# mosfet_board_v1.net
KiCad netlist of a schematic drawn in EAGLE
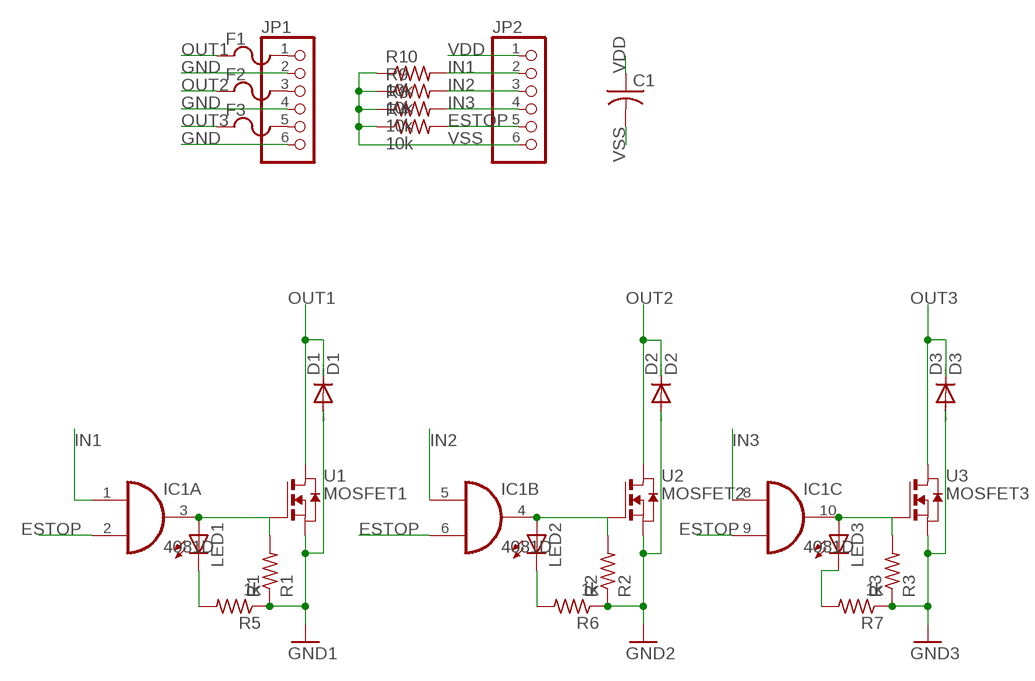
[diagram p0: schematic, sheet 1]

(export (version "E")
  (design (tool "Eeschema 10.0.6"))
  (components
    (comp (ref "C1")
      (value "C-USC0603")
      (footprint "eagle-import:C0603")
      (libsource (lib "eagle-import") (part "C-USC0603"))
    )
    (comp (ref "D1")
      (value "D1")
      (footprint "eagle-import:DO41-10")
      (libsource (lib "eagle-import") (part "1N4004"))
    )
    (comp (ref "D2")
      (value "D2")
      (footprint "eagle-import:DO41-10")
      (libsource (lib "eagle-import") (part "1N4004"))
    )
    (comp (ref "D3")
      (value "D3")
      (footprint "eagle-import:DO41-10")
      (libsource (lib "eagle-import") (part "1N4004"))
    )
    (comp (ref "F1")
      (value "POLYFUSE")
      (footprint "eagle-import:1206")
      (libsource (lib "eagle-import") (part "POLYFUSE"))
    )
    (comp (ref "F2")
      (value "POLYFUSE")
      (footprint "eagle-import:1206")
      (libsource (lib "eagle-import") (part "POLYFUSE"))
    )
    (comp (ref "F3")
      (value "POLYFUSE")
      (footprint "eagle-import:1206")
      (libsource (lib "eagle-import") (part "POLYFUSE"))
    )
    (comp (ref "IC1")
      (value "4081D")
      (footprint "eagle-import:SO14")
      (libsource (lib "eagle-import") (part "4081D"))
    )
    (comp (ref "JP1")
      (value "PINHD-1X6")
      (footprint "eagle-import:1X06")
      (libsource (lib "eagle-import") (part "PINHD-1X6"))
    )
    (comp (ref "JP2")
      (value "PINHD-1X6")
      (footprint "eagle-import:1X06")
      (libsource (lib "eagle-import") (part "PINHD-1X6"))
    )
    (comp (ref "LED1")
      (value "LEDCHIPLED_0603")
      (footprint "eagle-import:CHIPLED_0603")
      (libsource (lib "eagle-import") (part "LEDCHIPLED_0603"))
    )
    (comp (ref "LED2")
      (value "LEDCHIPLED_0603")
      (footprint "eagle-import:CHIPLED_0603")
      (libsource (lib "eagle-import") (part "LEDCHIPLED_0603"))
    )
    (comp (ref "LED3")
      (value "LEDCHIPLED_0603")
      (footprint "eagle-import:CHIPLED_0603")
      (libsource (lib "eagle-import") (part "LEDCHIPLED_0603"))
    )
    (comp (ref "R1")
      (value "R1")
      (footprint "eagle-import:R0603")
      (libsource (lib "eagle-import") (part "resistor_R-US_R0603"))
    )
    (comp (ref "R2")
      (value "R2")
      (footprint "eagle-import:R0603")
      (libsource (lib "eagle-import") (part "resistor_R-US_R0603"))
    )
    (comp (ref "R3")
      (value "R3")
      (footprint "eagle-import:R0603")
      (libsource (lib "eagle-import") (part "resistor_R-US_R0603"))
    )
    (comp (ref "R4")
      (value "10k")
      (footprint "eagle-import:R0603")
      (libsource (lib "eagle-import") (part "R-US_R0603"))
    )
    (comp (ref "R5")
      (value "1k")
      (footprint "eagle-import:R0603")
      (libsource (lib "eagle-import") (part "resistor_R-US_R0603"))
    )
    (comp (ref "R6")
      (value "1k")
      (footprint "eagle-import:R0603")
      (libsource (lib "eagle-import") (part "resistor_R-US_R0603"))
    )
    (comp (ref "R7")
      (value "1k")
      (footprint "eagle-import:R0603")
      (libsource (lib "eagle-import") (part "resistor_R-US_R0603"))
    )
    (comp (ref "R8")
      (value "10k")
      (footprint "eagle-import:R0603")
      (libsource (lib "eagle-import") (part "R-US_R0603"))
    )
    (comp (ref "R9")
      (value "10k")
      (footprint "eagle-import:R0603")
      (libsource (lib "eagle-import") (part "R-US_R0603"))
    )
    (comp (ref "R10")
      (value "10k")
      (footprint "eagle-import:R0603")
      (libsource (lib "eagle-import") (part "R-US_R0603"))
    )
    (comp (ref "U1")
      (value "MOSFET1")
      (footprint "eagle-import:MOSFET")
      (libsource (lib "eagle-import") (part "MOSFET"))
    )
    (comp (ref "U2")
      (value "MOSFET2")
      (footprint "eagle-import:MOSFET")
      (libsource (lib "eagle-import") (part "MOSFET"))
    )
    (comp (ref "U3")
      (value "MOSFET3")
      (footprint "eagle-import:MOSFET")
      (libsource (lib "eagle-import") (part "MOSFET"))
    )
  )
  (nets
    (net (code "1") (name "/ESTOP") (class "Default")
      (node (ref "IC1") (pin "2") (pinfunction "I1_2") (pintype "input"))
      (node (ref "IC1") (pin "6") (pinfunction "I1_6") (pintype "input"))
      (node (ref "IC1") (pin "9") (pinfunction "I1_9") (pintype "input"))
      (node (ref "JP2") (pin "5") (pinfunction "5_5") (pintype "passive"))
      (node (ref "R4") (pin "2") (pinfunction "2_2") (pintype "passive"))
    )
    (net (code "2") (name "/IN1") (class "Default")
      (node (ref "IC1") (pin "1") (pinfunction "I0_1") (pintype "input"))
      (node (ref "JP2") (pin "2") (pinfunction "2_2") (pintype "passive"))
      (node (ref "R10") (pin "2") (pinfunction "2_2") (pintype "passive"))
    )
    (net (code "3") (name "/IN2") (class "Default")
      (node (ref "IC1") (pin "5") (pinfunction "I0_5") (pintype "input"))
      (node (ref "JP2") (pin "3") (pinfunction "3_3") (pintype "passive"))
      (node (ref "R9") (pin "2") (pinfunction "2_2") (pintype "passive"))
    )
    (net (code "4") (name "/IN3") (class "Default")
      (node (ref "IC1") (pin "8") (pinfunction "I0_8") (pintype "input"))
      (node (ref "JP2") (pin "4") (pinfunction "4_4") (pintype "passive"))
      (node (ref "R8") (pin "2") (pinfunction "2_2") (pintype "passive"))
    )
    (net (code "5") (name "/OUT1") (class "Default")
      (node (ref "D1") (pin "C") (pinfunction "C_C") (pintype "passive"))
      (node (ref "F1") (pin "1") (pinfunction "1_1") (pintype "passive"))
      (node (ref "U1") (pin "P$2") (pinfunction "D_P$2") (pintype "passive"))
    )
    (net (code "6") (name "/OUT2") (class "Default")
      (node (ref "D2") (pin "C") (pinfunction "C_C") (pintype "passive"))
      (node (ref "F2") (pin "1") (pinfunction "1_1") (pintype "passive"))
      (node (ref "U2") (pin "P$2") (pinfunction "D_P$2") (pintype "passive"))
    )
    (net (code "7") (name "/OUT3") (class "Default")
      (node (ref "D3") (pin "C") (pinfunction "C_C") (pintype "passive"))
      (node (ref "F3") (pin "1") (pinfunction "1_1") (pintype "passive"))
      (node (ref "U3") (pin "P$2") (pinfunction "D_P$2") (pintype "passive"))
    )
    (net (code "8") (name "/VDD") (class "Default")
      (node (ref "C1") (pin "1") (pinfunction "1_1") (pintype "passive"))
      (node (ref "JP2") (pin "1") (pinfunction "1_1") (pintype "passive"))
    )
    (net (code "9") (name "/VSS") (class "Default")
      (node (ref "C1") (pin "2") (pinfunction "2_2") (pintype "passive"))
      (node (ref "JP2") (pin "6") (pinfunction "6_6") (pintype "passive"))
      (node (ref "R10") (pin "1") (pinfunction "1_1") (pintype "passive"))
      (node (ref "R4") (pin "1") (pinfunction "1_1") (pintype "passive"))
      (node (ref "R8") (pin "1") (pinfunction "1_1") (pintype "passive"))
      (node (ref "R9") (pin "1") (pinfunction "1_1") (pintype "passive"))
    )
    (net (code "10") (name "GND1") (class "Default")
      (node (ref "D1") (pin "A") (pinfunction "A_A") (pintype "passive"))
      (node (ref "D2") (pin "A") (pinfunction "A_A") (pintype "passive"))
      (node (ref "D3") (pin "A") (pinfunction "A_A") (pintype "passive"))
      (node (ref "JP1") (pin "2") (pinfunction "2_2") (pintype "passive"))
      (node (ref "JP1") (pin "4") (pinfunction "4_4") (pintype "passive"))
      (node (ref "JP1") (pin "6") (pinfunction "6_6") (pintype "passive"))
      (node (ref "R1") (pin "1") (pinfunction "1_1") (pintype "passive"))
      (node (ref "R2") (pin "1") (pinfunction "1_1") (pintype "passive"))
      (node (ref "R3") (pin "1") (pinfunction "1_1") (pintype "passive"))
      (node (ref "R5") (pin "1") (pinfunction "1_1") (pintype "passive"))
      (node (ref "R6") (pin "1") (pinfunction "1_1") (pintype "passive"))
      (node (ref "R7") (pin "1") (pinfunction "1_1") (pintype "passive"))
      (node (ref "U1") (pin "P$3") (pinfunction "S_P$3") (pintype "passive"))
      (node (ref "U2") (pin "P$3") (pinfunction "S_P$3") (pintype "passive"))
      (node (ref "U3") (pin "P$3") (pinfunction "S_P$3") (pintype "passive"))
    )
    (net (code "11") (name "Net-(F1-Pad2)") (class "Default")
      (node (ref "F1") (pin "2") (pinfunction "2_2") (pintype "passive"))
      (node (ref "JP1") (pin "1") (pinfunction "1_1") (pintype "passive"))
    )
    (net (code "12") (name "Net-(F2-Pad2)") (class "Default")
      (node (ref "F2") (pin "2") (pinfunction "2_2") (pintype "passive"))
      (node (ref "JP1") (pin "3") (pinfunction "3_3") (pintype "passive"))
    )
    (net (code "13") (name "Net-(F3-Pad2)") (class "Default")
      (node (ref "F3") (pin "2") (pinfunction "2_2") (pintype "passive"))
      (node (ref "JP1") (pin "5") (pinfunction "5_5") (pintype "passive"))
    )
    (net (code "14") (name "Net-(IC1A-O)") (class "Default")
      (node (ref "IC1") (pin "3") (pinfunction "O_3") (pintype "output"))
      (node (ref "LED1") (pin "A") (pinfunction "A_A") (pintype "passive"))
      (node (ref "R1") (pin "2") (pinfunction "2_2") (pintype "passive"))
      (node (ref "U1") (pin "P$1") (pinfunction "G_P$1") (pintype "passive"))
    )
    (net (code "15") (name "Net-(IC1B-O)") (class "Default")
      (node (ref "IC1") (pin "4") (pinfunction "O_4") (pintype "output"))
      (node (ref "LED2") (pin "A") (pinfunction "A_A") (pintype "passive"))
      (node (ref "R2") (pin "2") (pinfunction "2_2") (pintype "passive"))
      (node (ref "U2") (pin "P$1") (pinfunction "G_P$1") (pintype "passive"))
    )
    (net (code "16") (name "Net-(IC1C-O)") (class "Default")
      (node (ref "IC1") (pin "10") (pinfunction "O_10") (pintype "output"))
      (node (ref "LED3") (pin "A") (pinfunction "A_A") (pintype "passive"))
      (node (ref "R3") (pin "2") (pinfunction "2_2") (pintype "passive"))
      (node (ref "U3") (pin "P$1") (pinfunction "G_P$1") (pintype "passive"))
    )
    (net (code "17") (name "Net-(LED1-PadC)") (class "Default")
      (node (ref "LED1") (pin "C") (pinfunction "C_C") (pintype "passive"))
      (node (ref "R5") (pin "2") (pinfunction "2_2") (pintype "passive"))
    )
    (net (code "18") (name "Net-(LED2-PadC)") (class "Default")
      (node (ref "LED2") (pin "C") (pinfunction "C_C") (pintype "passive"))
      (node (ref "R6") (pin "2") (pinfunction "2_2") (pintype "passive"))
    )
    (net (code "19") (name "Net-(LED3-PadC)") (class "Default")
      (node (ref "LED3") (pin "C") (pinfunction "C_C") (pintype "passive"))
      (node (ref "R7") (pin "2") (pinfunction "2_2") (pintype "passive"))
    )
  )
)
